# ocd.net
KiCad netlist of a schematic drawn in EAGLE
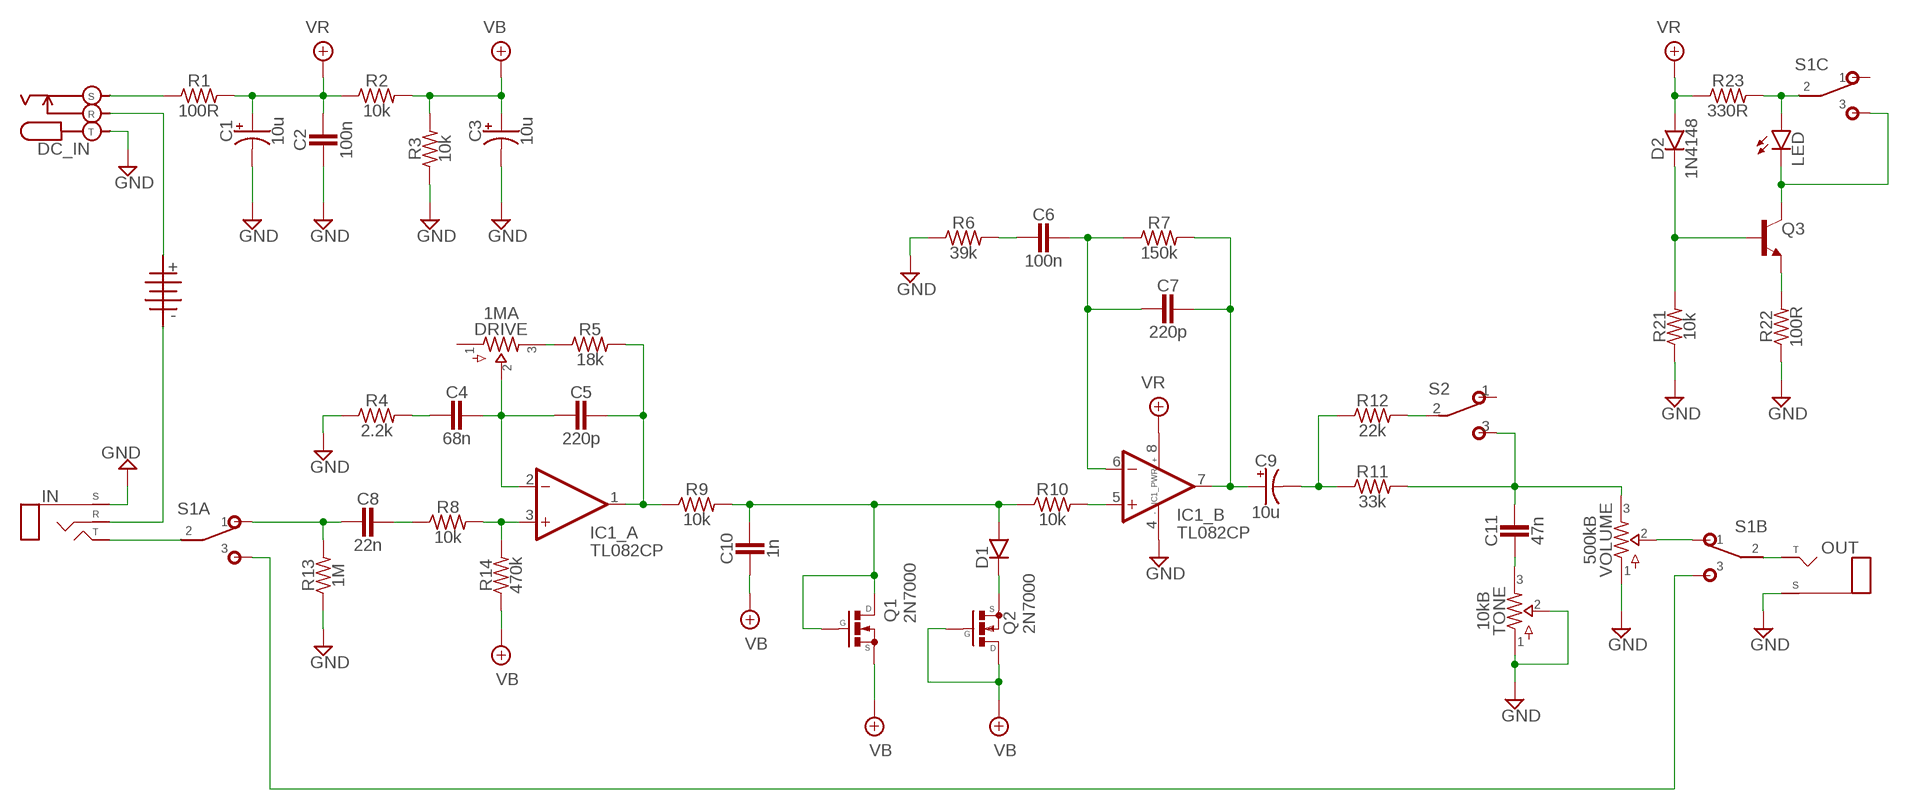
[diagram p0: schematic, sheet 1]

(export (version "E")
  (design (tool "Eeschema 10.0.6"))
  (components
    (comp (ref "1")
      (value "BATTERY")
      (footprint "eagle-import:TWO_PADS")
      (libsource (lib "eagle-import") (part "BATTERY"))
    )
    (comp (ref "C1")
      (value "10u")
      (footprint "eagle-import:050_020")
      (libsource (lib "eagle-import") (part "0500"))
    )
    (comp (ref "C2")
      (value "100n")
      (footprint "eagle-import:BOX_SMALL")
      (libsource (lib "eagle-import") (part "CER/FILMBOX.1"))
    )
    (comp (ref "C3")
      (value "10u")
      (footprint "eagle-import:050_020")
      (libsource (lib "eagle-import") (part "0500"))
    )
    (comp (ref "C4")
      (value "68n")
      (footprint "eagle-import:BOX_SMALL")
      (libsource (lib "eagle-import") (part "CER/FILMBOX.1"))
    )
    (comp (ref "C5")
      (value "220p")
      (footprint "eagle-import:BOX_SMALL")
      (libsource (lib "eagle-import") (part "CER/FILMBOX.1"))
    )
    (comp (ref "C6")
      (value "100n")
      (footprint "eagle-import:BOX_SMALL")
      (libsource (lib "eagle-import") (part "CER/FILMBOX.1"))
    )
    (comp (ref "C7")
      (value "220p")
      (footprint "eagle-import:BOX_SMALL")
      (libsource (lib "eagle-import") (part "CER/FILMBOX.1"))
    )
    (comp (ref "C8")
      (value "22n")
      (footprint "eagle-import:BOX_SMALL")
      (libsource (lib "eagle-import") (part "CER/FILMBOX.1"))
    )
    (comp (ref "C9")
      (value "10u")
      (footprint "eagle-import:050_020")
      (libsource (lib "eagle-import") (part "0500"))
    )
    (comp (ref "C10")
      (value "1n")
      (footprint "eagle-import:BOX_SMALL")
      (libsource (lib "eagle-import") (part "CER/FILMBOX.1"))
    )
    (comp (ref "C11")
      (value "47n")
      (footprint "eagle-import:BOX_SMALL")
      (libsource (lib "eagle-import") (part "CER/FILMBOX.1"))
    )
    (comp (ref "D1")
      (value "DO41.2")
      (footprint "eagle-import:DO41-2")
      (libsource (lib "eagle-import") (part "DO41.2"))
    )
    (comp (ref "D2")
      (value "1N4148")
      (footprint "eagle-import:DO41-2")
      (libsource (lib "eagle-import") (part "DO41.2"))
    )
    (comp (ref "DC_IN")
      (value "DC_KOBICONNPGR")
      (footprint "eagle-import:PGR")
      (libsource (lib "eagle-import") (part "DC_KOBICONNPGR"))
    )
    (comp (ref "DRIVE")
      (value "1MA")
      (footprint "eagle-import:16MM")
      (libsource (lib "eagle-import") (part "POTS16MM"))
    )
    (comp (ref "IC1")
      (value "TL082CP")
      (footprint "eagle-import:DIL0")
      (libsource (lib "eagle-import") (part "DUALTH"))
    )
    (comp (ref "IN")
      (value "STEREO")
      (footprint "eagle-import:STEREO_PCB")
      (libsource (lib "eagle-import") (part "STEREO"))
    )
    (comp (ref "LED")
      (value "LED")
      (footprint "eagle-import:3MM_D")
      (libsource (lib "eagle-import") (part "LED"))
    )
    (comp (ref "OUT")
      (value "MONO")
      (footprint "eagle-import:TWO_PADS")
      (libsource (lib "eagle-import") (part "MONO"))
    )
    (comp (ref "Q1")
      (value "2N7000")
      (footprint "eagle-import:TO92-")
      (libsource (lib "eagle-import") (part "2N7000"))
    )
    (comp (ref "Q2")
      (value "2N7000")
      (footprint "eagle-import:TO92-")
      (libsource (lib "eagle-import") (part "2N7000"))
    )
    (comp (ref "Q3")
      (value "2N3904")
      (footprint "eagle-import:TO92-")
      (libsource (lib "eagle-import") (part "2N3904"))
    )
    (comp (ref "R1")
      (value "100R")
      (footprint "eagle-import:R0207_3")
      (libsource (lib "eagle-import") (part "R_.3B"))
    )
    (comp (ref "R2")
      (value "10k")
      (footprint "eagle-import:R0207_3")
      (libsource (lib "eagle-import") (part "R_.3B"))
    )
    (comp (ref "R3")
      (value "10k")
      (footprint "eagle-import:R0207_3")
      (libsource (lib "eagle-import") (part "R_.3B"))
    )
    (comp (ref "R4")
      (value "2.2k")
      (footprint "eagle-import:R0207_3")
      (libsource (lib "eagle-import") (part "R_.3B"))
    )
    (comp (ref "R5")
      (value "18k")
      (footprint "eagle-import:R0207_3")
      (libsource (lib "eagle-import") (part "R_.3B"))
    )
    (comp (ref "R6")
      (value "39k")
      (footprint "eagle-import:R0207_3")
      (libsource (lib "eagle-import") (part "R_.3B"))
    )
    (comp (ref "R7")
      (value "150k")
      (footprint "eagle-import:R0207_3")
      (libsource (lib "eagle-import") (part "R_.3B"))
    )
    (comp (ref "R8")
      (value "10k")
      (footprint "eagle-import:R0207_3")
      (libsource (lib "eagle-import") (part "R_.3B"))
    )
    (comp (ref "R9")
      (value "10k")
      (footprint "eagle-import:R0207_3")
      (libsource (lib "eagle-import") (part "R_.3B"))
    )
    (comp (ref "R10")
      (value "10k")
      (footprint "eagle-import:R0207_3")
      (libsource (lib "eagle-import") (part "R_.3B"))
    )
    (comp (ref "R11")
      (value "33k")
      (footprint "eagle-import:R0207_3")
      (libsource (lib "eagle-import") (part "R_.3B"))
    )
    (comp (ref "R12")
      (value "22k")
      (footprint "eagle-import:R0207_3")
      (libsource (lib "eagle-import") (part "R_.3B"))
    )
    (comp (ref "R13")
      (value "1M")
      (footprint "eagle-import:R0207_3")
      (libsource (lib "eagle-import") (part "R_.3B"))
    )
    (comp (ref "R14")
      (value "470k")
      (footprint "eagle-import:R0207_3")
      (libsource (lib "eagle-import") (part "R_.3B"))
    )
    (comp (ref "R21")
      (value "10k")
      (footprint "eagle-import:R0207_3")
      (libsource (lib "eagle-import") (part "R_.3B"))
    )
    (comp (ref "R22")
      (value "100R")
      (footprint "eagle-import:R0207_3")
      (libsource (lib "eagle-import") (part "R_.3B"))
    )
    (comp (ref "R23")
      (value "330R")
      (footprint "eagle-import:R0207_3")
      (libsource (lib "eagle-import") (part "R_.3B"))
    )
    (comp (ref "S1")
      (value "3PDT")
      (footprint "eagle-import:3PDT")
      (libsource (lib "eagle-import") (part "3PDT"))
    )
    (comp (ref "S2")
      (value "SPDT")
      (footprint "eagle-import:M9040P")
      (libsource (lib "eagle-import") (part "SPDT"))
    )
    (comp (ref "TONE")
      (value "10kB")
      (footprint "eagle-import:16MM")
      (libsource (lib "eagle-import") (part "POTS16MM"))
    )
    (comp (ref "VOLUME")
      (value "500kB")
      (footprint "eagle-import:16MM")
      (libsource (lib "eagle-import") (part "POTS16MM"))
    )
  )
  (nets
    (net (code "1") (name "GND") (class "Default")
      (node (ref "C1") (pin "-") (pinfunction "-_-") (pintype "passive"))
      (node (ref "C2") (pin "2") (pinfunction "2_2") (pintype "passive"))
      (node (ref "C3") (pin "-") (pinfunction "-_-") (pintype "passive"))
      (node (ref "DC_IN") (pin "TIP") (pinfunction "T_TIP") (pintype "bidirectional"))
      (node (ref "IC1") (pin "4") (pinfunction "V-_4") (pintype "power_in"))
      (node (ref "IN") (pin "P$1") (pinfunction "S_P$1") (pintype "passive"))
      (node (ref "OUT") (pin "S") (pinfunction "SLEEVE_S") (pintype "passive"))
      (node (ref "R13") (pin "1") (pinfunction "1_1") (pintype "passive"))
      (node (ref "R21") (pin "1") (pinfunction "1_1") (pintype "passive"))
      (node (ref "R22") (pin "1") (pinfunction "1_1") (pintype "passive"))
      (node (ref "R3") (pin "1") (pinfunction "1_1") (pintype "passive"))
      (node (ref "R4") (pin "1") (pinfunction "1_1") (pintype "passive"))
      (node (ref "R6") (pin "1") (pinfunction "1_1") (pintype "passive"))
      (node (ref "TONE") (pin "1") (pinfunction "1_1") (pintype "passive"))
      (node (ref "TONE") (pin "2") (pinfunction "2_2") (pintype "passive"))
      (node (ref "VOLUME") (pin "1") (pinfunction "1_1") (pintype "passive"))
    )
    (net (code "2") (name "Net-(1-P$1)") (class "Default")
      (node (ref "1") (pin "T") (pinfunction "P$1_T") (pintype "bidirectional"))
      (node (ref "DC_IN") (pin "RING") (pinfunction "R_RING") (pintype "bidirectional"))
    )
    (net (code "3") (name "Net-(1-P$2)") (class "Default")
      (node (ref "1") (pin "S") (pinfunction "P$2_S") (pintype "bidirectional"))
      (node (ref "IN") (pin "P$2") (pinfunction "R_P$2") (pintype "passive"))
    )
    (net (code "4") (name "Net-(C4-Pad2)") (class "Default")
      (node (ref "C4") (pin "2") (pinfunction "2_2") (pintype "passive"))
      (node (ref "R4") (pin "2") (pinfunction "2_2") (pintype "passive"))
    )
    (net (code "5") (name "Net-(C6-Pad2)") (class "Default")
      (node (ref "C6") (pin "2") (pinfunction "2_2") (pintype "passive"))
      (node (ref "R6") (pin "2") (pinfunction "2_2") (pintype "passive"))
    )
    (net (code "6") (name "Net-(C8-Pad1)") (class "Default")
      (node (ref "C8") (pin "1") (pinfunction "1_1") (pintype "passive"))
      (node (ref "R8") (pin "1") (pinfunction "1_1") (pintype "passive"))
    )
    (net (code "7") (name "Net-(C9-Pad-)") (class "Default")
      (node (ref "C9") (pin "-") (pinfunction "-_-") (pintype "passive"))
      (node (ref "R11") (pin "1") (pinfunction "1_1") (pintype "passive"))
      (node (ref "R12") (pin "1") (pinfunction "1_1") (pintype "passive"))
    )
    (net (code "8") (name "Net-(C11-Pad2)") (class "Default")
      (node (ref "C11") (pin "2") (pinfunction "2_2") (pintype "passive"))
      (node (ref "TONE") (pin "3") (pinfunction "3_3") (pintype "passive"))
    )
    (net (code "9") (name "Net-(DC_IN-S)") (class "Default")
      (node (ref "DC_IN") (pin "SLEEVE") (pinfunction "S_SLEEVE") (pintype "bidirectional"))
      (node (ref "R1") (pin "1") (pinfunction "1_1") (pintype "passive"))
    )
    (net (code "10") (name "Net-(DRIVE-Pad3)") (class "Default")
      (node (ref "DRIVE") (pin "3") (pinfunction "3_3") (pintype "passive"))
      (node (ref "R5") (pin "1") (pinfunction "1_1") (pintype "passive"))
    )
    (net (code "11") (name "Net-(IC1A-+IN)") (class "Default")
      (node (ref "IC1") (pin "3") (pinfunction "+IN_3") (pintype "input"))
      (node (ref "R14") (pin "2") (pinfunction "2_2") (pintype "passive"))
      (node (ref "R8") (pin "2") (pinfunction "2_2") (pintype "passive"))
    )
    (net (code "12") (name "Net-(IC1A--IN)") (class "Default")
      (node (ref "C4") (pin "1") (pinfunction "1_1") (pintype "passive"))
      (node (ref "C5") (pin "2") (pinfunction "2_2") (pintype "passive"))
      (node (ref "DRIVE") (pin "2") (pinfunction "2_2") (pintype "passive"))
      (node (ref "IC1") (pin "2") (pinfunction "-IN_2") (pintype "input"))
    )
    (net (code "13") (name "Net-(IC1A-OUT)") (class "Default")
      (node (ref "C5") (pin "1") (pinfunction "1_1") (pintype "passive"))
      (node (ref "IC1") (pin "1") (pinfunction "OUT_1") (pintype "output"))
      (node (ref "R5") (pin "2") (pinfunction "2_2") (pintype "passive"))
      (node (ref "R9") (pin "1") (pinfunction "1_1") (pintype "passive"))
    )
    (net (code "14") (name "Net-(IC1B-+IN)") (class "Default")
      (node (ref "IC1") (pin "5") (pinfunction "+IN_5") (pintype "input"))
      (node (ref "R10") (pin "2") (pinfunction "2_2") (pintype "passive"))
    )
    (net (code "15") (name "Net-(IC1B--IN)") (class "Default")
      (node (ref "C6") (pin "1") (pinfunction "1_1") (pintype "passive"))
      (node (ref "C7") (pin "2") (pinfunction "2_2") (pintype "passive"))
      (node (ref "IC1") (pin "6") (pinfunction "-IN_6") (pintype "input"))
      (node (ref "R7") (pin "1") (pinfunction "1_1") (pintype "passive"))
    )
    (net (code "16") (name "Net-(IC1B-OUT)") (class "Default")
      (node (ref "C7") (pin "1") (pinfunction "1_1") (pintype "passive"))
      (node (ref "C9") (pin "+") (pinfunction "+_+") (pintype "passive"))
      (node (ref "IC1") (pin "7") (pinfunction "OUT_7") (pintype "output"))
      (node (ref "R7") (pin "2") (pinfunction "2_2") (pintype "passive"))
    )
    (net (code "17") (name "Net-(IN-T)") (class "Default")
      (node (ref "IN") (pin "P$3") (pinfunction "T_P$3") (pintype "passive"))
      (node (ref "S1") (pin "A2") (pinfunction "2_A2") (pintype "passive"))
    )
    (net (code "18") (name "Net-(LED-A)") (class "Default")
      (node (ref "LED") (pin "ANODE") (pinfunction "A_ANODE") (pintype "passive"))
      (node (ref "R23") (pin "2") (pinfunction "2_2") (pintype "passive"))
      (node (ref "S1") (pin "C2") (pinfunction "2_C2") (pintype "passive"))
    )
    (net (code "19") (name "Net-(LED-C)") (class "Default")
      (node (ref "LED") (pin "P$1") (pinfunction "C_P$1") (pintype "passive"))
      (node (ref "Q3") (pin "1") (pinfunction "C_1") (pintype "passive"))
      (node (ref "S1") (pin "C3") (pinfunction "3_C3") (pintype "passive"))
    )
    (net (code "20") (name "Net-(OUT-TIP)") (class "Default")
      (node (ref "OUT") (pin "T") (pinfunction "TIP_T") (pintype "passive"))
      (node (ref "S1") (pin "B2") (pinfunction "2_B2") (pintype "passive"))
    )
    (net (code "21") (name "Net-(Q1-D)") (class "Default")
      (node (ref "C10") (pin "1") (pinfunction "1_1") (pintype "passive"))
      (node (ref "D1") (pin "A") (pinfunction "A_A") (pintype "passive"))
      (node (ref "Q1") (pin "1") (pinfunction "D_1") (pintype "passive"))
      (node (ref "Q1") (pin "2") (pinfunction "G_2") (pintype "passive"))
      (node (ref "R10") (pin "1") (pinfunction "1_1") (pintype "passive"))
      (node (ref "R9") (pin "2") (pinfunction "2_2") (pintype "passive"))
    )
    (net (code "22") (name "Net-(Q2-S)") (class "Default")
      (node (ref "D1") (pin "C") (pinfunction "C_C") (pintype "passive"))
      (node (ref "Q2") (pin "3") (pinfunction "S_3") (pintype "passive"))
    )
    (net (code "23") (name "Net-(Q3-B)") (class "Default")
      (node (ref "D2") (pin "C") (pinfunction "C_C") (pintype "passive"))
      (node (ref "Q3") (pin "2") (pinfunction "B_2") (pintype "passive"))
      (node (ref "R21") (pin "2") (pinfunction "2_2") (pintype "passive"))
    )
    (net (code "24") (name "Net-(Q3-E)") (class "Default")
      (node (ref "Q3") (pin "3") (pinfunction "E_3") (pintype "passive"))
      (node (ref "R22") (pin "2") (pinfunction "2_2") (pintype "passive"))
    )
    (net (code "25") (name "Net-(S1A-1)") (class "Default")
      (node (ref "C8") (pin "2") (pinfunction "2_2") (pintype "passive"))
      (node (ref "R13") (pin "2") (pinfunction "2_2") (pintype "passive"))
      (node (ref "S1") (pin "A1") (pinfunction "1_A1") (pintype "passive"))
    )
    (net (code "26") (name "Net-(S1A-3)") (class "Default")
      (node (ref "S1") (pin "A3") (pinfunction "3_A3") (pintype "passive"))
      (node (ref "S1") (pin "B3") (pinfunction "3_B3") (pintype "passive"))
    )
    (net (code "27") (name "Net-(S1B-1)") (class "Default")
      (node (ref "S1") (pin "B1") (pinfunction "1_B1") (pintype "passive"))
      (node (ref "VOLUME") (pin "2") (pinfunction "2_2") (pintype "passive"))
    )
    (net (code "28") (name "Net-(S2-P)") (class "Default")
      (node (ref "R12") (pin "2") (pinfunction "2_2") (pintype "passive"))
      (node (ref "S2") (pin "2") (pinfunction "P_2") (pintype "passive"))
    )
    (net (code "29") (name "Net-(S2-S)") (class "Default")
      (node (ref "C11") (pin "1") (pinfunction "1_1") (pintype "passive"))
      (node (ref "R11") (pin "2") (pinfunction "2_2") (pintype "passive"))
      (node (ref "S2") (pin "3") (pinfunction "S_3") (pintype "passive"))
      (node (ref "VOLUME") (pin "3") (pinfunction "3_3") (pintype "passive"))
    )
    (net (code "30") (name "VB") (class "Default")
      (node (ref "C10") (pin "2") (pinfunction "2_2") (pintype "passive"))
      (node (ref "C3") (pin "+") (pinfunction "+_+") (pintype "passive"))
      (node (ref "Q1") (pin "3") (pinfunction "S_3") (pintype "passive"))
      (node (ref "Q2") (pin "1") (pinfunction "D_1") (pintype "passive"))
      (node (ref "Q2") (pin "2") (pinfunction "G_2") (pintype "passive"))
      (node (ref "R14") (pin "1") (pinfunction "1_1") (pintype "passive"))
      (node (ref "R2") (pin "2") (pinfunction "2_2") (pintype "passive"))
      (node (ref "R3") (pin "2") (pinfunction "2_2") (pintype "passive"))
    )
    (net (code "31") (name "VR") (class "Default")
      (node (ref "C1") (pin "+") (pinfunction "+_+") (pintype "passive"))
      (node (ref "C2") (pin "1") (pinfunction "1_1") (pintype "passive"))
      (node (ref "D2") (pin "A") (pinfunction "A_A") (pintype "passive"))
      (node (ref "IC1") (pin "8") (pinfunction "V+_8") (pintype "power_in"))
      (node (ref "R1") (pin "2") (pinfunction "2_2") (pintype "passive"))
      (node (ref "R2") (pin "1") (pinfunction "1_1") (pintype "passive"))
      (node (ref "R23") (pin "1") (pinfunction "1_1") (pintype "passive"))
    )
    (net (code "32") (name "unconnected-(DRIVE-Pad1)") (class "Default")
      (node (ref "DRIVE") (pin "1") (pinfunction "1_1") (pintype "passive"))
    )
    (net (code "33") (name "unconnected-(S1C-1-PadC1)") (class "Default")
      (node (ref "S1") (pin "C1") (pinfunction "1_C1") (pintype "passive"))
    )
    (net (code "34") (name "unconnected-(S2-O-Pad1)") (class "Default")
      (node (ref "S2") (pin "1") (pinfunction "O_1") (pintype "passive"))
    )
  )
)
